# Sheet2.net
KiCad netlist of a schematic drawn in Altium Designer
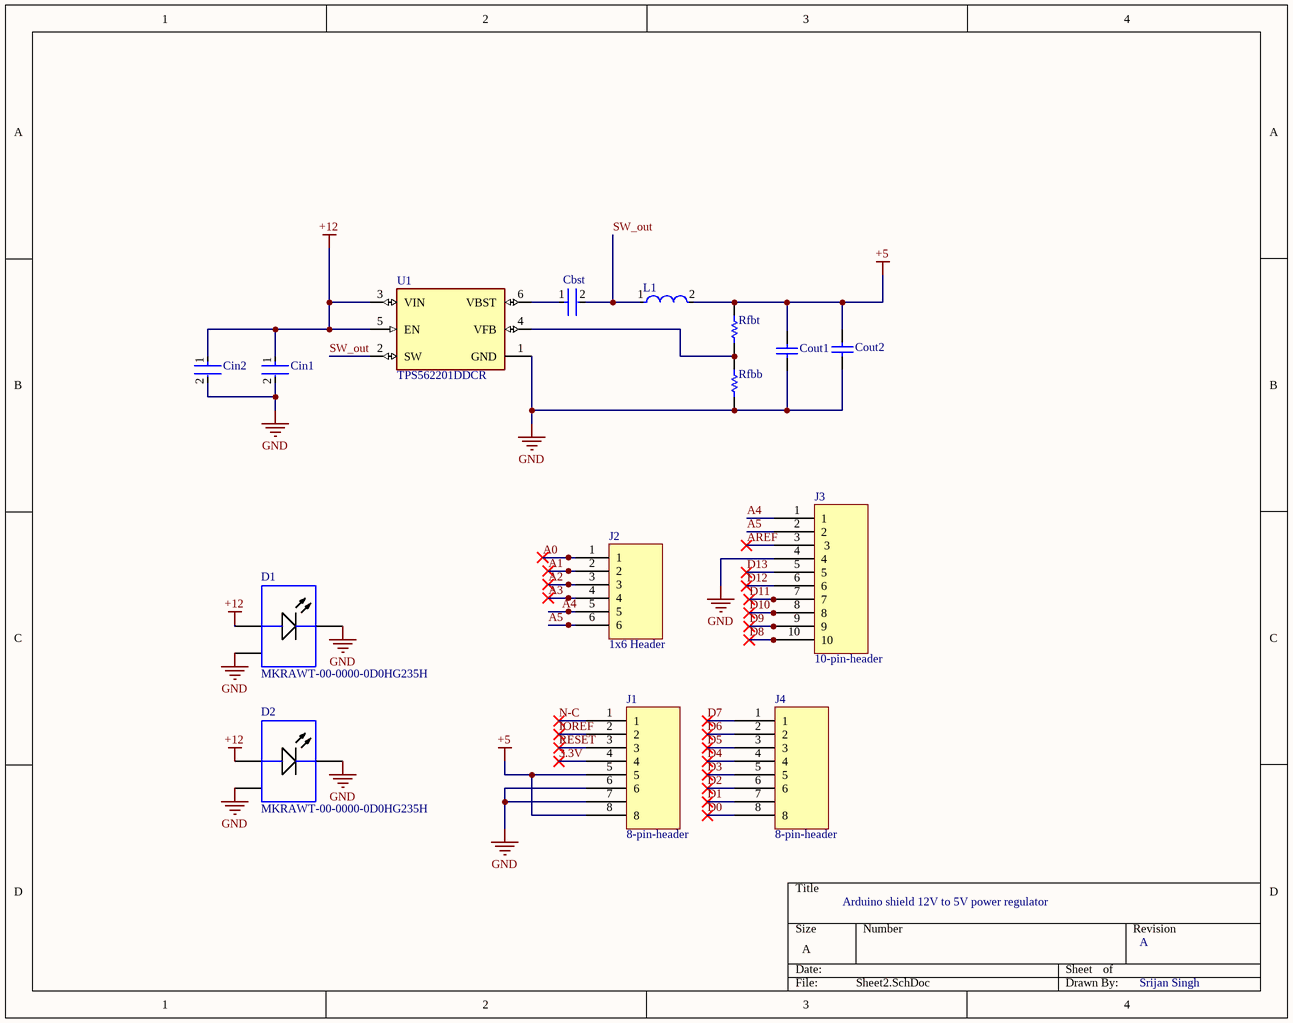
[diagram p0: Sheet2.SchDoc]

(export (version "E")
  (design (tool "Eeschema 10.0.6"))
  (components
    (comp (ref "Cbst")
      (value "08053C104KAT2A")
      (footprint "FP-0805-L_2_01_0_2-W_1_25-IPC_C")
      (description "General Purpose Ceramic Capacitor, 0805, 100nF, 10%, X7R, 0.15, 25V")
      (fields (field (name "TOLERANCE") "10%") (field (name "VOLTAGE") "25V"))
      (libsource (lib "Altium Content Vault") (part "02cd4be3c70576c341d710602a673aa"))
    )
    (comp (ref "Cin1")
      (value "GRM188R60J106ME47D")
      (footprint "FP-GRM188-0_1-e0_2_0_55-IPC_A")
      (description "Chip Multilayer Ceramic Capacitors for General Purpose, 0603, 10uF, X5R, 15%, 20%, 6.3V")
      (fields (field (name "VOLTAGE") "6.3V") (field (name "TOLERANCE") "20%"))
      (libsource (lib "Altium Content Vault") (part "02cd4be3c70576c341d710602a673aa"))
    )
    (comp (ref "Cin2")
      (value "GRM188R60J106ME47D")
      (footprint "FP-GRM188-0_1-e0_2_0_55-IPC_A")
      (description "Chip Multilayer Ceramic Capacitors for General Purpose, 0603, 10uF, X5R, 15%, 20%, 6.3V")
      (fields (field (name "VOLTAGE") "6.3V") (field (name "TOLERANCE") "20%"))
      (libsource (lib "Altium Content Vault") (part "02cd4be3c70576c341d710602a673aa"))
    )
    (comp (ref "Cout1")
      (value "C1608X5R1A226M080AC")
      (footprint "CAPC1608X100X20ML10")
      (description "Chip Capacitor, 22 uF, +/- 20%, 10 V, -55 to 85 degC, 0603 (1608 Metric), RoHS, Tape and Reel")
      (fields (field (name "MANUFACTURER") "TDK") (field (name "TOLERANCE") "±20%"))
      (libsource (lib "Altium Content Vault") (part "CAP-NP-2"))
    )
    (comp (ref "Cout2")
      (value "C1608X5R1A226M080AC")
      (footprint "CAPC1608X100X20ML10")
      (description "Chip Capacitor, 22 uF, +/- 20%, 10 V, -55 to 85 degC, 0603 (1608 Metric), RoHS, Tape and Reel")
      (fields (field (name "MANUFACTURER") "TDK") (field (name "TOLERANCE") "±20%"))
      (libsource (lib "Altium Content Vault") (part "CAP-NP-2"))
    )
    (comp (ref "D1")
      (value "MKRAWT-00-0000-0D0HG235H")
      (footprint "CREE-MK-R-2_V")
      (description "LED, White, 12 V, 2-Pin SMD, RoHS, Tape and Reel")
      (libsource (lib "Altium Content Vault") (part "LED_WHITE-3"))
    )
    (comp (ref "D2")
      (value "MKRAWT-00-0000-0D0HG235H")
      (footprint "CREE-MK-R-2_V")
      (description "LED, White, 12 V, 2-Pin SMD, RoHS, Tape and Reel")
      (libsource (lib "Altium Content Vault") (part "LED_WHITE-3"))
    )
    (comp (ref "J1")
      (value "8-pin-header")
      (footprint "8pin")
      (libsource (lib "Schlib1") (part "8-pin-header"))
    )
    (comp (ref "J2")
      (value "1x6 Header")
      (footprint "6pin")
      (libsource (lib "Schlib1") (part "6-Pin-Header"))
    )
    (comp (ref "J3")
      (value "10-pin-header")
      (footprint "10pin")
      (libsource (lib "Schlib1") (part "10-pin-header"))
    )
    (comp (ref "J4")
      (value "8-pin-header")
      (footprint "8pin")
      (libsource (lib "Schlib1") (part "8-pin-header"))
    )
    (comp (ref "L1")
      (value "NRS8030T3R3MJGJ")
      (footprint "FP-NRS8030-MFG")
      (description "Inductor Power Shielded Wirewound 3.3uH 20% 100KHz Ferrite 4.2A 24.7mΩ DCR T/R")
      (fields (field (name "TOLERANCE") "20%"))
      (libsource (lib "Altium Content Vault") (part "725321dda6339637d4d059423bc1c3c"))
    )
    (comp (ref "Rfbb")
      (value "ERJ2RKF1002X")
      (footprint "RESC1005X40X25LL05T05")
      (description "Chip Resistor, 10 KOhm, +/- 1%, 0.1 W, -55 to 155 degC, 0402 (1005 Metric), RoHS, Tape and Reel")
      (fields (field (name "TOLERANCE") "1%") (field (name "MANUFACTURER") "Panasonic"))
      (libsource (lib "Altium Content Vault") (part "RES-2"))
    )
    (comp (ref "Rfbt")
      (value "CRCW020156K2FNED")
      (footprint "RESC0603X28X15NL05T05")
      (fields (field (name "MANUFACTURER") "Vishay Dale"))
      (libsource (lib "Altium Content Vault") (part "RES"))
    )
    (comp (ref "U1")
      (value "TPS562201DDCR")
      (footprint "FP-DDC0006A-IPC_C")
      (description "IC REG BUCK ADJ 2A TSOT23-6")
      (libsource (lib "Altium Content Vault") (part "957e164956730ea4bf6293280af19fc"))
    )
  )
  (nets
    (net (code "1") (name "+5") (class "Default")
      (node (ref "Cout1") (pin "2") (pinfunction "2_2") (pintype "passive"))
      (node (ref "Cout2") (pin "2") (pinfunction "2_2") (pintype "passive"))
      (node (ref "J1") (pin "5") (pinfunction "5_5") (pintype "passive"))
      (node (ref "J1") (pin "8") (pinfunction "8_8") (pintype "passive"))
      (node (ref "L1") (pin "2") (pinfunction "2_2") (pintype "passive"))
      (node (ref "Rfbt") (pin "2") (pinfunction "2_2") (pintype "passive"))
    )
    (net (code "2") (name "+12") (class "Default")
      (node (ref "Cin1") (pin "1") (pinfunction "1_1") (pintype "passive"))
      (node (ref "Cin2") (pin "1") (pinfunction "1_1") (pintype "passive"))
      (node (ref "D1") (pin "1") (pinfunction "A_1") (pintype "passive"))
      (node (ref "D2") (pin "1") (pinfunction "A_1") (pintype "passive"))
      (node (ref "U1") (pin "3") (pinfunction "VIN_3") (pintype "bidirectional"))
      (node (ref "U1") (pin "5") (pinfunction "EN_5") (pintype "input"))
    )
    (net (code "3") (name "/3.3V") (class "Default")
      (node (ref "J1") (pin "4") (pinfunction "4_4") (pintype "passive+no_connect"))
    )
    (net (code "4") (name "/A0") (class "Default")
      (node (ref "J2") (pin "1") (pinfunction "1_1") (pintype "passive+no_connect"))
    )
    (net (code "5") (name "/A1") (class "Default")
      (node (ref "J2") (pin "2") (pinfunction "2_2") (pintype "passive+no_connect"))
    )
    (net (code "6") (name "/A2") (class "Default")
      (node (ref "J2") (pin "3") (pinfunction "3_3") (pintype "passive+no_connect"))
    )
    (net (code "7") (name "/A3") (class "Default")
      (node (ref "J2") (pin "4") (pinfunction "4_4") (pintype "passive+no_connect"))
    )
    (net (code "8") (name "/A4") (class "Default")
      (node (ref "J2") (pin "5") (pinfunction "5_5") (pintype "passive"))
      (node (ref "J3") (pin "1") (pinfunction "1_1") (pintype "passive"))
    )
    (net (code "9") (name "/A5") (class "Default")
      (node (ref "J2") (pin "6") (pinfunction "6_6") (pintype "passive"))
      (node (ref "J3") (pin "2") (pinfunction "2_2") (pintype "passive"))
    )
    (net (code "10") (name "/AREF") (class "Default")
      (node (ref "J3") (pin "3") (pinfunction "_3_3") (pintype "passive+no_connect"))
    )
    (net (code "11") (name "/D0") (class "Default")
      (node (ref "J4") (pin "8") (pinfunction "8_8") (pintype "passive+no_connect"))
    )
    (net (code "12") (name "/D1") (class "Default")
      (node (ref "J4") (pin "7") (pintype "passive+no_connect"))
    )
    (net (code "13") (name "/D2") (class "Default")
      (node (ref "J4") (pin "6") (pinfunction "6_6") (pintype "passive+no_connect"))
    )
    (net (code "14") (name "/D3") (class "Default")
      (node (ref "J4") (pin "5") (pinfunction "5_5") (pintype "passive+no_connect"))
    )
    (net (code "15") (name "/D4") (class "Default")
      (node (ref "J4") (pin "4") (pinfunction "4_4") (pintype "passive+no_connect"))
    )
    (net (code "16") (name "/D5") (class "Default")
      (node (ref "J4") (pin "3") (pinfunction "3_3") (pintype "passive+no_connect"))
    )
    (net (code "17") (name "/D6") (class "Default")
      (node (ref "J4") (pin "2") (pinfunction "2_2") (pintype "passive+no_connect"))
    )
    (net (code "18") (name "/D7") (class "Default")
      (node (ref "J4") (pin "1") (pinfunction "1_1") (pintype "passive+no_connect"))
    )
    (net (code "19") (name "/D8") (class "Default")
      (node (ref "J3") (pin "10") (pinfunction "10_10") (pintype "passive+no_connect"))
    )
    (net (code "20") (name "/D9") (class "Default")
      (node (ref "J3") (pin "9") (pinfunction "9_9") (pintype "passive+no_connect"))
    )
    (net (code "21") (name "/D10") (class "Default")
      (node (ref "J3") (pin "8") (pinfunction "8_8") (pintype "passive+no_connect"))
    )
    (net (code "22") (name "/D11") (class "Default")
      (node (ref "J3") (pin "7") (pinfunction "7_7") (pintype "passive+no_connect"))
    )
    (net (code "23") (name "/D12") (class "Default")
      (node (ref "J3") (pin "6") (pinfunction "6_6") (pintype "passive+no_connect"))
    )
    (net (code "24") (name "/D13") (class "Default")
      (node (ref "J3") (pin "5") (pinfunction "5_5") (pintype "passive+no_connect"))
    )
    (net (code "25") (name "/IOREF") (class "Default")
      (node (ref "J1") (pin "2") (pinfunction "2_2") (pintype "passive+no_connect"))
    )
    (net (code "26") (name "/N-C") (class "Default")
      (node (ref "J1") (pin "1") (pinfunction "1_1") (pintype "passive+no_connect"))
    )
    (net (code "27") (name "/RESET") (class "Default")
      (node (ref "J1") (pin "3") (pinfunction "3_3") (pintype "passive+no_connect"))
    )
    (net (code "28") (name "/SW_out") (class "Default")
      (node (ref "Cbst") (pin "2") (pinfunction "2_2") (pintype "passive"))
      (node (ref "L1") (pin "1") (pinfunction "1_1") (pintype "passive"))
      (node (ref "U1") (pin "2") (pinfunction "SW_2") (pintype "bidirectional"))
    )
    (net (code "29") (name "GND") (class "Default")
      (node (ref "Cin1") (pin "2") (pinfunction "2_2") (pintype "passive"))
      (node (ref "Cin2") (pin "2") (pinfunction "2_2") (pintype "passive"))
      (node (ref "Cout1") (pin "1") (pinfunction "1_1") (pintype "passive"))
      (node (ref "Cout2") (pin "1") (pinfunction "1_1") (pintype "passive"))
      (node (ref "D1") (pin "2") (pinfunction "K_2") (pintype "passive"))
      (node (ref "D1") (pin "3") (pinfunction "EP_3") (pintype "passive"))
      (node (ref "D2") (pin "2") (pinfunction "K_2") (pintype "passive"))
      (node (ref "D2") (pin "3") (pinfunction "EP_3") (pintype "passive"))
      (node (ref "J1") (pin "6") (pinfunction "6_6") (pintype "passive"))
      (node (ref "J1") (pin "7") (pintype "passive"))
      (node (ref "J3") (pin "4") (pinfunction "4_4") (pintype "passive"))
      (node (ref "Rfbb") (pin "1") (pinfunction "1_1") (pintype "passive"))
      (node (ref "U1") (pin "1") (pinfunction "GND_1") (pintype "power_in"))
    )
    (net (code "30") (name "Net-(U1-VBST)") (class "Default")
      (node (ref "Cbst") (pin "1") (pinfunction "1_1") (pintype "passive"))
      (node (ref "U1") (pin "6") (pinfunction "VBST_6") (pintype "bidirectional"))
    )
    (net (code "31") (name "Net-(U1-VFB)") (class "Default")
      (node (ref "Rfbb") (pin "2") (pinfunction "2_2") (pintype "passive"))
      (node (ref "Rfbt") (pin "1") (pinfunction "1_1") (pintype "passive"))
      (node (ref "U1") (pin "4") (pinfunction "VFB_4") (pintype "bidirectional"))
    )
  )
)
